# DAC.net
KiCad netlist of a schematic drawn in Altium Designer
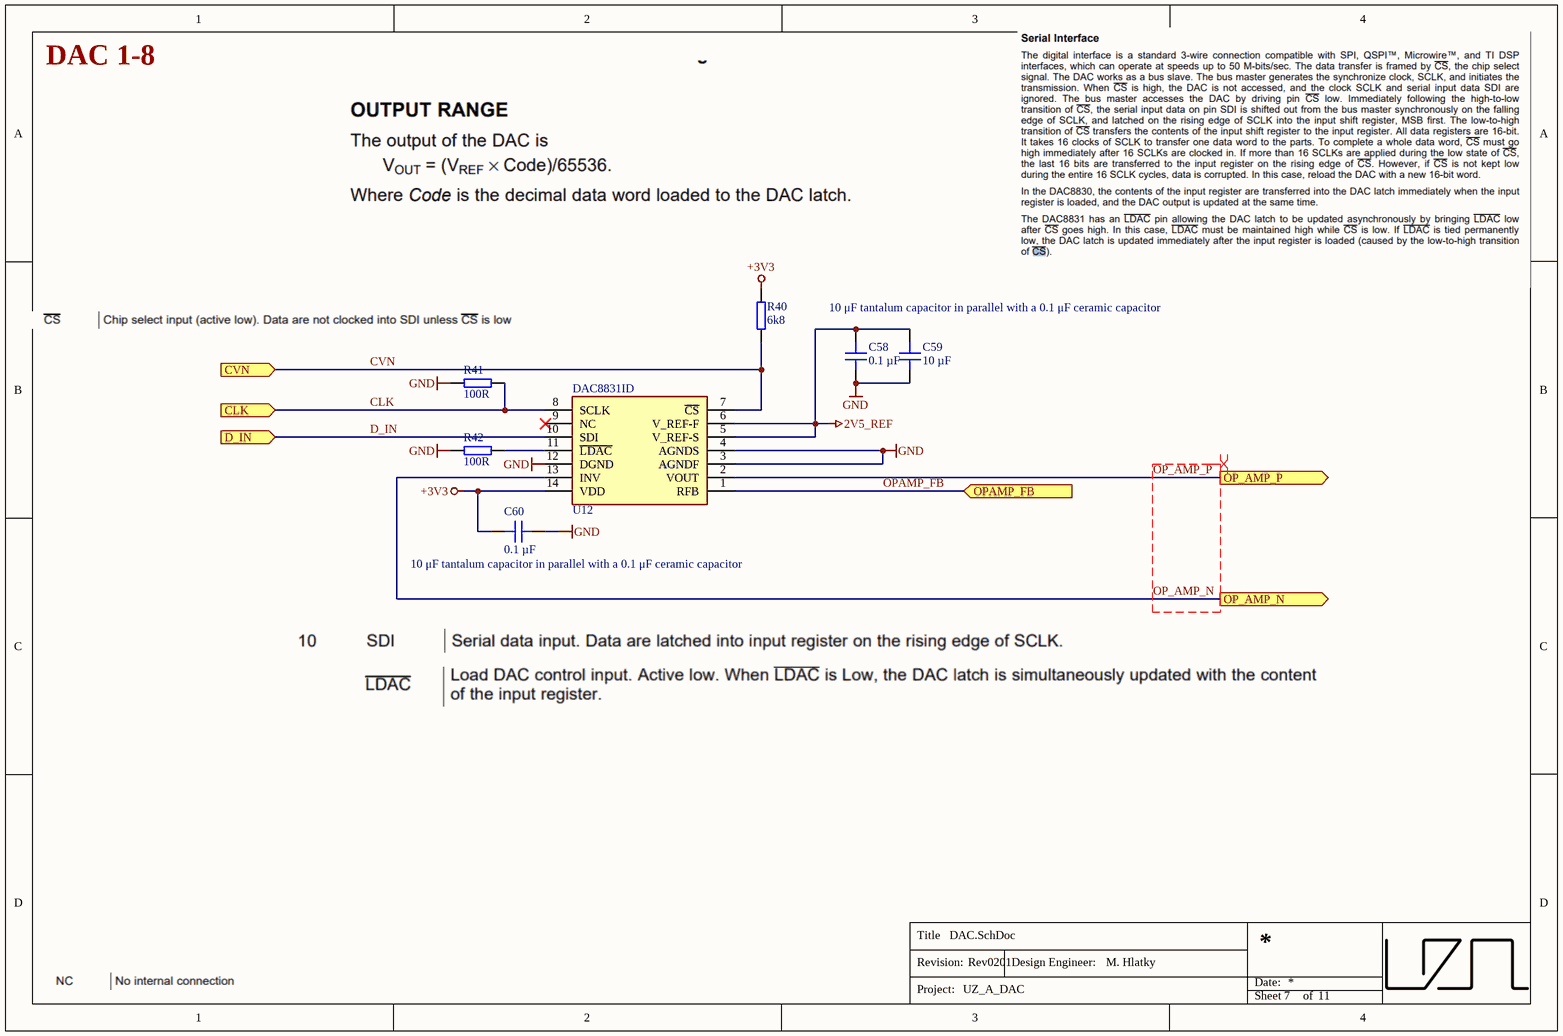
[diagram p0: DAC.SchDoc]

(export (version "E")
  (design (tool "Eeschema 10.0.6"))
  (components
    (comp (ref "C58")
      (value "0.1 µF")
      (footprint "C_0603")
      (description "Capacitor 0603, 50 VDC, 0.1 µF, X7R")
      (fields
        (field (name "MANUFACTURER PART NUMBER") "C0603X104K5RAC7411")
        (field (name "MANUFACTURER") "KEMET")
        (field (name "CREATED FROM") "MGremer")
      )
      (libsource (lib "user") (part "Capacitor"))
    )
    (comp (ref "C59")
      (value "10 µF")
      (footprint "C_1206")
      (description "Capacitor 1206, 50 VDC, 10 µF, X5R")
      (fields
        (field (name "MANUFACTURER PART NUMBER") "GRT31CR61H106KE01L")
        (field (name "MANUFACTURER") "Murata Electronics")
        (field (name "CREATED FROM") "MGremer")
      )
      (libsource (lib "user") (part "Capacitor"))
    )
    (comp (ref "C60")
      (value "0.1 µF")
      (footprint "C_0603")
      (description "Capacitor 0603, 50 VDC, 0.1 µF, X7R")
      (fields
        (field (name "MANUFACTURER PART NUMBER") "C0603X104K5RAC7411")
        (field (name "MANUFACTURER") "KEMET")
        (field (name "CREATED FROM") "MGremer")
      )
      (libsource (lib "user") (part "Capacitor"))
    )
    (comp (ref "R40")
      (value "6k8")
      (footprint "RES 0603_1608")
      (description "SMD resistor E24 series")
      (fields
        (field (name "MANUFACTURER PART NUMBER") "RK73B1JTTDD682J")
        (field (name "MANUFACTURER") "KOA Speer")
        (field (name "CREATED FROM") "MGremer")
      )
      (libsource (lib "user") (part "Resistor"))
    )
    (comp (ref "R41")
      (value "100R")
      (footprint "RES 0603_1608")
      (description "SMD resistor 1%")
      (fields
        (field (name "MANUFACTURER PART NUMBER") "AC0603FR-13100RL")
        (field (name "MANUFACTURER") "Yageo")
        (field (name "CREATED FROM") "MGremer")
      )
      (libsource (lib "user") (part "Resistor"))
    )
    (comp (ref "R42")
      (value "100R")
      (footprint "RES 0603_1608")
      (description "SMD resistor 1%")
      (fields
        (field (name "MANUFACTURER PART NUMBER") "AC0603FR-13100RL")
        (field (name "MANUFACTURER") "Yageo")
        (field (name "CREATED FROM") "MGremer")
      )
      (libsource (lib "user") (part "Resistor"))
    )
    (comp (ref "U12")
      (value "DAC8831ID")
      (footprint "SOIC127P600X175-14N")
      (description "16-Bit, Ultra-Low Power, Voltage-OutputcDigital-to-Analog Converters")
      (fields (field (name "MANUFACTURER") "TI") (field (name "CREATED FROM") "MHlatky"))
      (libsource (lib "user") (part "DAC8831ID"))
    )
  )
  (nets
    (net (code "1") (name "+3V3") (class "Default")
      (node (ref "C60") (pin "2") (pinfunction "2_2") (pintype "passive"))
      (node (ref "R40") (pin "2") (pinfunction "2_2") (pintype "passive"))
      (node (ref "U12") (pin "14") (pinfunction "VDD_14") (pintype "passive"))
    )
    (net (code "2") (name "/CLK") (class "Default")
      (node (ref "R41") (pin "1") (pinfunction "1_1") (pintype "passive"))
      (node (ref "U12") (pin "8") (pinfunction "SCLK_8") (pintype "passive"))
    )
    (net (code "3") (name "/CVN") (class "Default")
      (node (ref "R40") (pin "1") (pinfunction "1_1") (pintype "passive"))
      (node (ref "U12") (pin "7") (pinfunction "~{CS}_7") (pintype "passive"))
    )
    (net (code "4") (name "/D_IN") (class "Default")
      (node (ref "U12") (pin "10") (pinfunction "SDI_10") (pintype "passive"))
    )
    (net (code "5") (name "/OPAMP_FB") (class "Default")
      (node (ref "U12") (pin "1") (pinfunction "RFB_1") (pintype "passive"))
    )
    (net (code "6") (name "/OP_AMP_N") (class "Default")
      (node (ref "U12") (pin "13") (pinfunction "INV_13") (pintype "passive"))
    )
    (net (code "7") (name "/OP_AMP_P") (class "Default")
      (node (ref "U12") (pin "2") (pinfunction "VOUT_2") (pintype "passive"))
    )
    (net (code "8") (name "2V5_REF") (class "Default")
      (node (ref "C58") (pin "1") (pinfunction "1_1") (pintype "passive"))
      (node (ref "C59") (pin "2") (pinfunction "2_2") (pintype "passive"))
      (node (ref "U12") (pin "5") (pinfunction "V_REF-S_5") (pintype "passive"))
      (node (ref "U12") (pin "6") (pinfunction "V_REF-F_6") (pintype "passive"))
    )
    (net (code "9") (name "GND") (class "Default")
      (node (ref "C58") (pin "2") (pinfunction "2_2") (pintype "passive"))
      (node (ref "C59") (pin "1") (pinfunction "1_1") (pintype "passive"))
      (node (ref "C60") (pin "1") (pinfunction "1_1") (pintype "passive"))
      (node (ref "R41") (pin "2") (pinfunction "2_2") (pintype "passive"))
      (node (ref "R42") (pin "2") (pinfunction "2_2") (pintype "passive"))
      (node (ref "U12") (pin "12") (pinfunction "DGND_12") (pintype "passive"))
      (node (ref "U12") (pin "3") (pinfunction "AGNDF_3") (pintype "passive"))
      (node (ref "U12") (pin "4") (pinfunction "AGNDS_4") (pintype "passive"))
    )
    (net (code "10") (name "Net-(U12-~{LDAC})") (class "Default")
      (node (ref "R42") (pin "1") (pinfunction "1_1") (pintype "passive"))
      (node (ref "U12") (pin "11") (pinfunction "~{LDAC}_11") (pintype "passive"))
    )
    (net (code "11") (name "unconnected-(U12-NC-Pad9)") (class "Default")
      (node (ref "U12") (pin "9") (pinfunction "NC_9") (pintype "passive+no_connect"))
    )
  )
)
